# Mainboard.net
KiCad netlist of a schematic drawn in Altium Designer
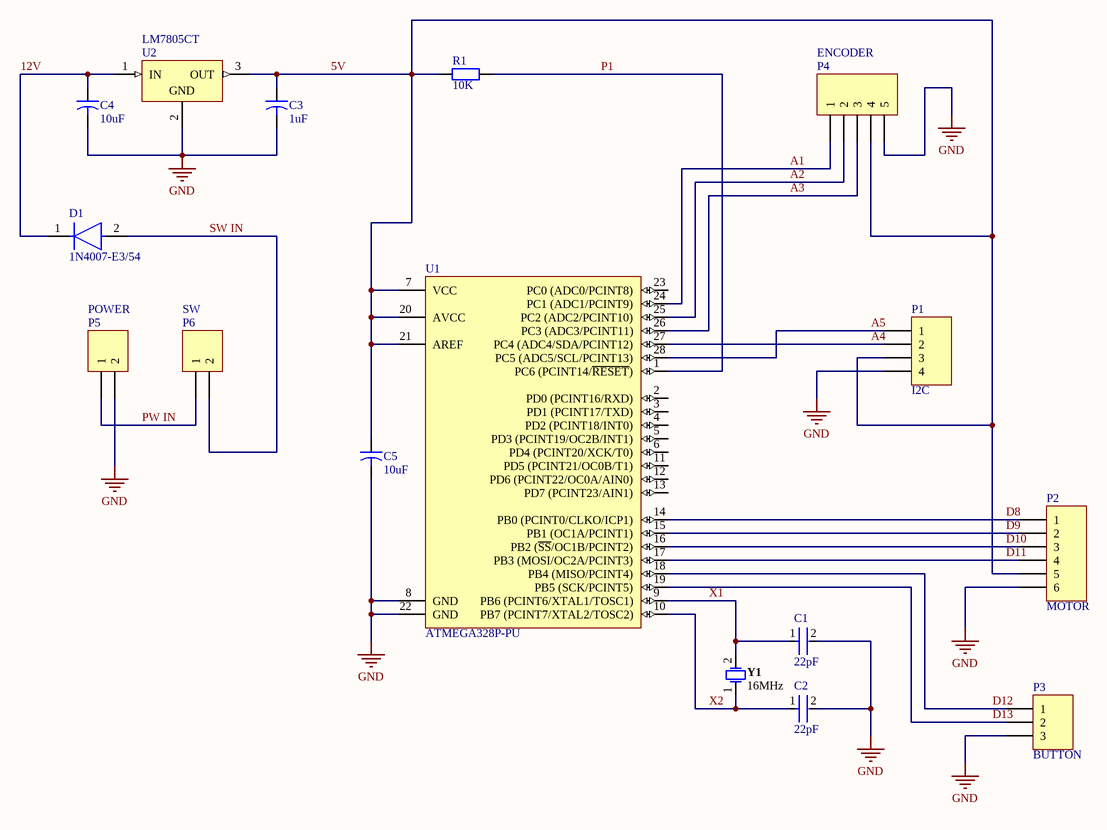
[diagram p0: Mainboard.SchDoc]

(export (version "E")
  (design (tool "Eeschema 10.0.6"))
  (components
    (comp (ref "C1")
      (value "22pF")
      (footprint "FP-RCE0DB-MFG")
      (description "Cap Ceramic 22pF 50V C0G ±5% Radial 2.5mm +125°C Ammo Pack")
      (fields (field (name "TOLERANCE") "5%"))
      (libsource (lib "Altium Content Vault") (part "b4654b650e69147ec39a6b967a45e02"))
    )
    (comp (ref "C2")
      (value "22pF")
      (footprint "FP-RCE0DB-MFG")
      (description "Cap Ceramic 22pF 50V C0G ±5% Radial 2.5mm +125°C Ammo Pack")
      (fields (field (name "TOLERANCE") "5%"))
      (libsource (lib "Altium Content Vault") (part "b4654b650e69147ec39a6b967a45e02"))
    )
    (comp (ref "C3")
      (value "1uF")
      (footprint "CAPR5-4X5")
      (description "Capacitor")
      (fields (field (name "PUBLISHER") "Altium Limited"))
      (libsource (lib "Miscellaneous Devices") (part "Cap2"))
    )
    (comp (ref "C4")
      (value "10uF")
      (footprint "CAPR5-4X5")
      (description "Capacitor")
      (fields (field (name "PUBLISHER") "Altium Limited"))
      (libsource (lib "Miscellaneous Devices") (part "Cap2"))
    )
    (comp (ref "C5")
      (value "10uF")
      (footprint "CAPR5-4X5")
      (description "Capacitor")
      (fields (field (name "PUBLISHER") "Altium Limited"))
      (libsource (lib "Miscellaneous Devices") (part "Cap2"))
    )
    (comp (ref "D1")
      (value "1N4007-E3/54")
      (footprint "FP-1N4007-MFG")
      (description "DIODE GEN PURP 1KV 1A DO204AL")
      (fields
        (field (name "OCTOPART") "https://octopart.com/1n4007-e3%2F54-vishay-39548207")
        (field (name "MANUFACTURER") "Vishay")
      )
      (libsource (lib "Altium Content Vault") (part "d7152d700b627762746794eb795d46e"))
    )
    (comp (ref "P1")
      (value "I2C")
      (footprint "HDR1X4")
      (description "Header, 4-Pin")
      (fields (field (name "PUBLISHER") "Altium Limited"))
      (libsource (lib "Miscellaneous Connectors") (part "Header 4"))
    )
    (comp (ref "P2")
      (value "MOTOR")
      (footprint "HDR1X6")
      (description "Header, 6-Pin")
      (fields (field (name "PUBLISHER") "Altium Limited"))
      (libsource (lib "Miscellaneous Connectors") (part "Header 6"))
    )
    (comp (ref "P3")
      (value "BUTTON")
      (footprint "HDR1X3")
      (description "Header, 3-Pin")
      (fields (field (name "PUBLISHER") "Altium Limited"))
      (libsource (lib "Miscellaneous Connectors") (part "Header 3"))
    )
    (comp (ref "P4")
      (value "ENCODER")
      (footprint "HDR1X5")
      (description "Header, 5-Pin")
      (fields (field (name "PUBLISHER") "Altium Limited"))
      (libsource (lib "Miscellaneous Connectors") (part "Header 5"))
    )
    (comp (ref "P5")
      (value "POWER")
      (footprint "HDR1X2")
      (description "Header, 2-Pin")
      (fields (field (name "PUBLISHER") "Altium Limited"))
      (libsource (lib "Miscellaneous Connectors") (part "Header 2"))
    )
    (comp (ref "P6")
      (value "SW")
      (footprint "HDR1X2")
      (description "Header, 2-Pin")
      (fields (field (name "PUBLISHER") "Altium Limited"))
      (libsource (lib "Miscellaneous Connectors") (part "Header 2"))
    )
    (comp (ref "R1")
      (value "10K")
      (footprint "AXIAL-0.4")
      (description "Resistor")
      (fields (field (name "PUBLISHER") "Altium Limited"))
      (libsource (lib "Miscellaneous Devices") (part "Res2"))
    )
    (comp (ref "U1")
      (value "ATMEGA328P-PU")
      (footprint "ATML-28P3")
      (fields (field (name "MANUFACTURER") "Atmel"))
      (libsource (lib "University of Moratuwa") (part "MC-8B-ATM48-IL28"))
    )
    (comp (ref "U2")
      (value "LM7805CT")
      (footprint "FAIR-TO-220-3")
      (description "Positive Voltage Regulator, 5 V, 1 A, -40 to 125 degC, 3-Pin TO-220, RoHS, Tube")
      (fields (field (name "MANUFACTURER") "FairchildSemiconductor"))
      (libsource (lib "Altium Content Vault") (part "FAIR-LM7805CT-TO220-3"))
    )
    (comp (ref "Y1")
      (value "16MHz")
      (footprint "FOX-FOXSLF160-20")
      (description "Resistance Weld Thru-Hole Crystal, 16 MHz, -20 to 70 degC, 2-Pin THD, RoHS, Bulk")
      (fields (field (name "TOLERANCE") "1%"))
      (libsource (lib "Altium Content Vault") (part "XTAL-1-2-2"))
    )
  )
  (nets
    (net (code "1") (name "/5V") (class "Default")
      (node (ref "C3") (pin "1") (pinfunction "1_1") (pintype "passive"))
      (node (ref "C5") (pin "1") (pinfunction "1_1") (pintype "passive"))
      (node (ref "P1") (pin "3") (pinfunction "3_3") (pintype "passive"))
      (node (ref "P2") (pin "5") (pinfunction "5_5") (pintype "passive"))
      (node (ref "P4") (pin "4") (pinfunction "4_4") (pintype "passive"))
      (node (ref "R1") (pin "1") (pinfunction "1_1") (pintype "passive"))
      (node (ref "U1") (pin "20") (pinfunction "AVCC_20") (pintype "power_in"))
      (node (ref "U1") (pin "21") (pinfunction "AREF_21") (pintype "power_in"))
      (node (ref "U1") (pin "7") (pinfunction "VCC_7") (pintype "power_in"))
      (node (ref "U2") (pin "3") (pinfunction "OUT_3") (pintype "output"))
    )
    (net (code "2") (name "/12V") (class "Default")
      (node (ref "C4") (pin "1") (pinfunction "1_1") (pintype "passive"))
      (node (ref "D1") (pin "1") (pinfunction "C_1") (pintype "passive"))
      (node (ref "U2") (pin "1") (pinfunction "IN_1") (pintype "input"))
    )
    (net (code "3") (name "/A1") (class "Default")
      (node (ref "P4") (pin "1") (pinfunction "1_1") (pintype "passive"))
      (node (ref "U1") (pin "24") (pinfunction "PC1_(ADC1/PCINT9)_24") (pintype "bidirectional"))
    )
    (net (code "4") (name "/A2") (class "Default")
      (node (ref "P4") (pin "2") (pinfunction "2_2") (pintype "passive"))
      (node (ref "U1") (pin "25") (pinfunction "PC2_(ADC2/PCINT10)_25") (pintype "bidirectional"))
    )
    (net (code "5") (name "/A3") (class "Default")
      (node (ref "P4") (pin "3") (pinfunction "3_3") (pintype "passive"))
      (node (ref "U1") (pin "26") (pinfunction "PC3_(ADC3/PCINT11)_26") (pintype "bidirectional"))
    )
    (net (code "6") (name "/A4") (class "Default")
      (node (ref "P1") (pin "2") (pinfunction "2_2") (pintype "passive"))
      (node (ref "U1") (pin "27") (pinfunction "PC4_(ADC4/SDA/PCINT12)_27") (pintype "bidirectional"))
    )
    (net (code "7") (name "/A5") (class "Default")
      (node (ref "P1") (pin "1") (pinfunction "1_1") (pintype "passive"))
      (node (ref "U1") (pin "28") (pinfunction "PC5_(ADC5/SCL/PCINT13)_28") (pintype "bidirectional"))
    )
    (net (code "8") (name "/D8") (class "Default")
      (node (ref "P2") (pin "1") (pinfunction "1_1") (pintype "passive"))
      (node (ref "U1") (pin "14") (pinfunction "PB0_(PCINT0/CLKO/ICP1)_14") (pintype "bidirectional"))
    )
    (net (code "9") (name "/D9") (class "Default")
      (node (ref "P2") (pin "2") (pinfunction "2_2") (pintype "passive"))
      (node (ref "U1") (pin "15") (pinfunction "PB1_(OC1A/PCINT1)_15") (pintype "bidirectional"))
    )
    (net (code "10") (name "/D10") (class "Default")
      (node (ref "P2") (pin "3") (pinfunction "3_3") (pintype "passive"))
      (node (ref "U1") (pin "16") (pinfunction "PB2_(~{SS}/OC1B/PCINT2)_16") (pintype "bidirectional"))
    )
    (net (code "11") (name "/D11") (class "Default")
      (node (ref "P2") (pin "4") (pinfunction "4_4") (pintype "passive"))
      (node (ref "U1") (pin "17") (pinfunction "PB3_(MOSI/OC2A/PCINT3)_17") (pintype "bidirectional"))
    )
    (net (code "12") (name "/D12") (class "Default")
      (node (ref "P3") (pin "1") (pinfunction "1_1") (pintype "passive"))
      (node (ref "U1") (pin "18") (pinfunction "PB4_(MISO/PCINT4)_18") (pintype "bidirectional"))
    )
    (net (code "13") (name "/D13") (class "Default")
      (node (ref "P3") (pin "2") (pinfunction "2_2") (pintype "passive"))
      (node (ref "U1") (pin "19") (pinfunction "PB5_(SCK/PCINT5)_19") (pintype "bidirectional"))
    )
    (net (code "14") (name "/P1") (class "Default")
      (node (ref "R1") (pin "2") (pinfunction "2_2") (pintype "passive"))
      (node (ref "U1") (pin "1") (pinfunction "PC6_(PCINT14/~{RESET})_1") (pintype "bidirectional"))
    )
    (net (code "15") (name "/PW IN") (class "Default")
      (node (ref "P5") (pin "1") (pinfunction "1_1") (pintype "passive"))
      (node (ref "P6") (pin "1") (pinfunction "1_1") (pintype "passive"))
    )
    (net (code "16") (name "/SW IN") (class "Default")
      (node (ref "D1") (pin "2") (pinfunction "A_2") (pintype "passive"))
      (node (ref "P6") (pin "2") (pinfunction "2_2") (pintype "passive"))
    )
    (net (code "17") (name "/X1") (class "Default")
      (node (ref "C1") (pin "1") (pinfunction "1_1") (pintype "passive"))
      (node (ref "U1") (pin "9") (pinfunction "PB6_(PCINT6/XTAL1/TOSC1)_9") (pintype "bidirectional"))
      (node (ref "Y1") (pin "2") (pinfunction "2_2") (pintype "passive"))
    )
    (net (code "18") (name "/X2") (class "Default")
      (node (ref "C2") (pin "1") (pinfunction "1_1") (pintype "passive"))
      (node (ref "U1") (pin "10") (pinfunction "PB7_(PCINT7/XTAL2/TOSC2)_10") (pintype "bidirectional"))
      (node (ref "Y1") (pin "1") (pinfunction "1_1") (pintype "passive"))
    )
    (net (code "19") (name "GND") (class "Default")
      (node (ref "C1") (pin "2") (pinfunction "2_2") (pintype "passive"))
      (node (ref "C2") (pin "2") (pinfunction "2_2") (pintype "passive"))
      (node (ref "C3") (pin "2") (pinfunction "2_2") (pintype "passive"))
      (node (ref "C4") (pin "2") (pinfunction "2_2") (pintype "passive"))
      (node (ref "C5") (pin "2") (pinfunction "2_2") (pintype "passive"))
      (node (ref "P1") (pin "4") (pinfunction "4_4") (pintype "passive"))
      (node (ref "P2") (pin "6") (pinfunction "6_6") (pintype "passive"))
      (node (ref "P3") (pin "3") (pinfunction "3_3") (pintype "passive"))
      (node (ref "P4") (pin "5") (pinfunction "5_5") (pintype "passive"))
      (node (ref "P5") (pin "2") (pinfunction "2_2") (pintype "passive"))
      (node (ref "U1") (pin "22") (pinfunction "GND_22") (pintype "power_in"))
      (node (ref "U1") (pin "8") (pinfunction "GND_8") (pintype "power_in"))
      (node (ref "U2") (pin "2") (pinfunction "GND_2") (pintype "power_in"))
    )
    (net (code "20") (name "unconnected-(U1-PC0_(ADC0{slash}PCINT8)-Pad23)") (class "Default")
      (node (ref "U1") (pin "23") (pinfunction "PC0_(ADC0/PCINT8)_23") (pintype "bidirectional"))
    )
    (net (code "21") (name "unconnected-(U1-PD0_(PCINT16{slash}RXD)-Pad2)") (class "Default")
      (node (ref "U1") (pin "2") (pinfunction "PD0_(PCINT16/RXD)_2") (pintype "bidirectional"))
    )
    (net (code "22") (name "unconnected-(U1-PD1_(PCINT17{slash}TXD)-Pad3)") (class "Default")
      (node (ref "U1") (pin "3") (pinfunction "PD1_(PCINT17/TXD)_3") (pintype "bidirectional"))
    )
    (net (code "23") (name "unconnected-(U1-PD2_(PCINT18{slash}INT0)-Pad4)") (class "Default")
      (node (ref "U1") (pin "4") (pinfunction "PD2_(PCINT18/INT0)_4") (pintype "bidirectional"))
    )
    (net (code "24") (name "unconnected-(U1-PD3_(PCINT19{slash}OC2B{slash}INT1)-Pad5)") (class "Default")
      (node (ref "U1") (pin "5") (pinfunction "PD3_(PCINT19/OC2B/INT1)_5") (pintype "bidirectional"))
    )
    (net (code "25") (name "unconnected-(U1-PD4_(PCINT20{slash}XCK{slash}T0)-Pad6)") (class "Default")
      (node (ref "U1") (pin "6") (pinfunction "PD4_(PCINT20/XCK/T0)_6") (pintype "bidirectional"))
    )
    (net (code "26") (name "unconnected-(U1-PD5_(PCINT21{slash}OC0B{slash}T1)-Pad11)") (class "Default")
      (node (ref "U1") (pin "11") (pinfunction "PD5_(PCINT21/OC0B/T1)_11") (pintype "bidirectional"))
    )
    (net (code "27") (name "unconnected-(U1-PD6_(PCINT22{slash}OC0A{slash}AIN0)-Pad12)") (class "Default")
      (node (ref "U1") (pin "12") (pinfunction "PD6_(PCINT22/OC0A/AIN0)_12") (pintype "bidirectional"))
    )
    (net (code "28") (name "unconnected-(U1-PD7_(PCINT23{slash}AIN1)-Pad13)") (class "Default")
      (node (ref "U1") (pin "13") (pinfunction "PD7_(PCINT23/AIN1)_13") (pintype "bidirectional"))
    )
  )
)
